# fabflash-mk-2_1-driver.net
KiCad netlist of a schematic drawn in EAGLE
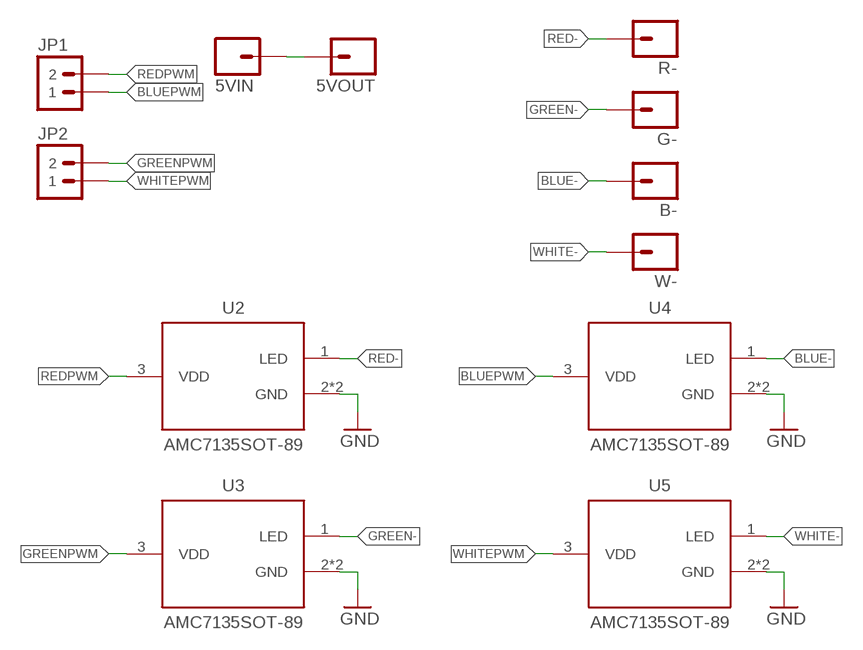
[diagram p0: schematic, sheet 1]

(export (version "E")
  (design (tool "Eeschema 10.0.6"))
  (components
    (comp (ref "5VIN")
      (value "M01SMD_2X3MM")
      (footprint "eagle-import:1X01_SMD_2X3MM")
      (libsource (lib "eagle-import") (part "M01SMD_2X3MM"))
    )
    (comp (ref "5VOUT")
      (value "M01SMD_2X3MM")
      (footprint "eagle-import:1X01_SMD_2X3MM")
      (libsource (lib "eagle-import") (part "M01SMD_2X3MM"))
    )
    (comp (ref "B-")
      (value "M01SMD_2X3MM")
      (footprint "eagle-import:1X01_SMD_2X3MM")
      (libsource (lib "eagle-import") (part "M01SMD_2X3MM"))
    )
    (comp (ref "G-")
      (value "M01SMD_2X3MM")
      (footprint "eagle-import:1X01_SMD_2X3MM")
      (libsource (lib "eagle-import") (part "M01SMD_2X3MM"))
    )
    (comp (ref "JP1")
      (value "M02PTH-2MM")
      (footprint "eagle-import:1X02-2MM-PTH")
      (libsource (lib "eagle-import") (part "M02PTH-2MM"))
    )
    (comp (ref "JP2")
      (value "M02PTH-2MM")
      (footprint "eagle-import:1X02-2MM-PTH")
      (libsource (lib "eagle-import") (part "M02PTH-2MM"))
    )
    (comp (ref "R-")
      (value "M01SMD_2X3MM")
      (footprint "eagle-import:1X01_SMD_2X3MM")
      (libsource (lib "eagle-import") (part "M01SMD_2X3MM"))
    )
    (comp (ref "U2")
      (value "AMC7135SOT-89")
      (footprint "eagle-import:SOT89")
      (libsource (lib "eagle-import") (part "AMC7135SOT-89"))
    )
    (comp (ref "U3")
      (value "AMC7135SOT-89")
      (footprint "eagle-import:SOT89")
      (libsource (lib "eagle-import") (part "AMC7135SOT-89"))
    )
    (comp (ref "U4")
      (value "AMC7135SOT-89")
      (footprint "eagle-import:SOT89")
      (libsource (lib "eagle-import") (part "AMC7135SOT-89"))
    )
    (comp (ref "U5")
      (value "AMC7135SOT-89")
      (footprint "eagle-import:SOT89")
      (libsource (lib "eagle-import") (part "AMC7135SOT-89"))
    )
    (comp (ref "W-")
      (value "M01SMD_2X3MM")
      (footprint "eagle-import:1X01_SMD_2X3MM")
      (libsource (lib "eagle-import") (part "M01SMD_2X3MM"))
    )
  )
  (nets
    (net (code "1") (name "BLUE-") (class "Default")
      (node (ref "B-") (pin "P$1") (pinfunction "1_P$1") (pintype "passive"))
      (node (ref "U4") (pin "1") (pinfunction "LED_1") (pintype "bidirectional"))
    )
    (net (code "2") (name "BLUEPWM") (class "Default")
      (node (ref "JP1") (pin "P$1") (pinfunction "1_P$1") (pintype "passive"))
      (node (ref "U4") (pin "3") (pinfunction "VDD_3") (pintype "bidirectional"))
    )
    (net (code "3") (name "GND") (class "Default")
      (node (ref "U2") (pin "2") (pinfunction "GND_2") (pintype "bidirectional"))
      (node (ref "U2") (pin "4") (pinfunction "GND_4") (pintype "bidirectional"))
      (node (ref "U3") (pin "2") (pinfunction "GND_2") (pintype "bidirectional"))
      (node (ref "U3") (pin "4") (pinfunction "GND_4") (pintype "bidirectional"))
      (node (ref "U4") (pin "2") (pinfunction "GND_2") (pintype "bidirectional"))
      (node (ref "U4") (pin "4") (pinfunction "GND_4") (pintype "bidirectional"))
      (node (ref "U5") (pin "2") (pinfunction "GND_2") (pintype "bidirectional"))
      (node (ref "U5") (pin "4") (pinfunction "GND_4") (pintype "bidirectional"))
    )
    (net (code "4") (name "GREEN-") (class "Default")
      (node (ref "G-") (pin "P$1") (pinfunction "1_P$1") (pintype "passive"))
      (node (ref "U3") (pin "1") (pinfunction "LED_1") (pintype "bidirectional"))
    )
    (net (code "5") (name "GREENPWM") (class "Default")
      (node (ref "JP2") (pin "P$2") (pinfunction "2_P$2") (pintype "passive"))
      (node (ref "U3") (pin "3") (pinfunction "VDD_3") (pintype "bidirectional"))
    )
    (net (code "6") (name "Net-(5VIN-1)") (class "Default")
      (node (ref "5VIN") (pin "P$1") (pinfunction "1_P$1") (pintype "passive"))
      (node (ref "5VOUT") (pin "P$1") (pinfunction "1_P$1") (pintype "passive"))
    )
    (net (code "7") (name "RED-") (class "Default")
      (node (ref "R-") (pin "P$1") (pinfunction "1_P$1") (pintype "passive"))
      (node (ref "U2") (pin "1") (pinfunction "LED_1") (pintype "bidirectional"))
    )
    (net (code "8") (name "REDPWM") (class "Default")
      (node (ref "JP1") (pin "P$2") (pinfunction "2_P$2") (pintype "passive"))
      (node (ref "U2") (pin "3") (pinfunction "VDD_3") (pintype "bidirectional"))
    )
    (net (code "9") (name "WHITE-") (class "Default")
      (node (ref "U5") (pin "1") (pinfunction "LED_1") (pintype "bidirectional"))
      (node (ref "W-") (pin "P$1") (pinfunction "1_P$1") (pintype "passive"))
    )
    (net (code "10") (name "WHITEPWM") (class "Default")
      (node (ref "JP2") (pin "P$1") (pinfunction "1_P$1") (pintype "passive"))
      (node (ref "U5") (pin "3") (pinfunction "VDD_3") (pintype "bidirectional"))
    )
  )
)
